# Matrice.net
KiCad netlist of a schematic drawn in Altium Designer
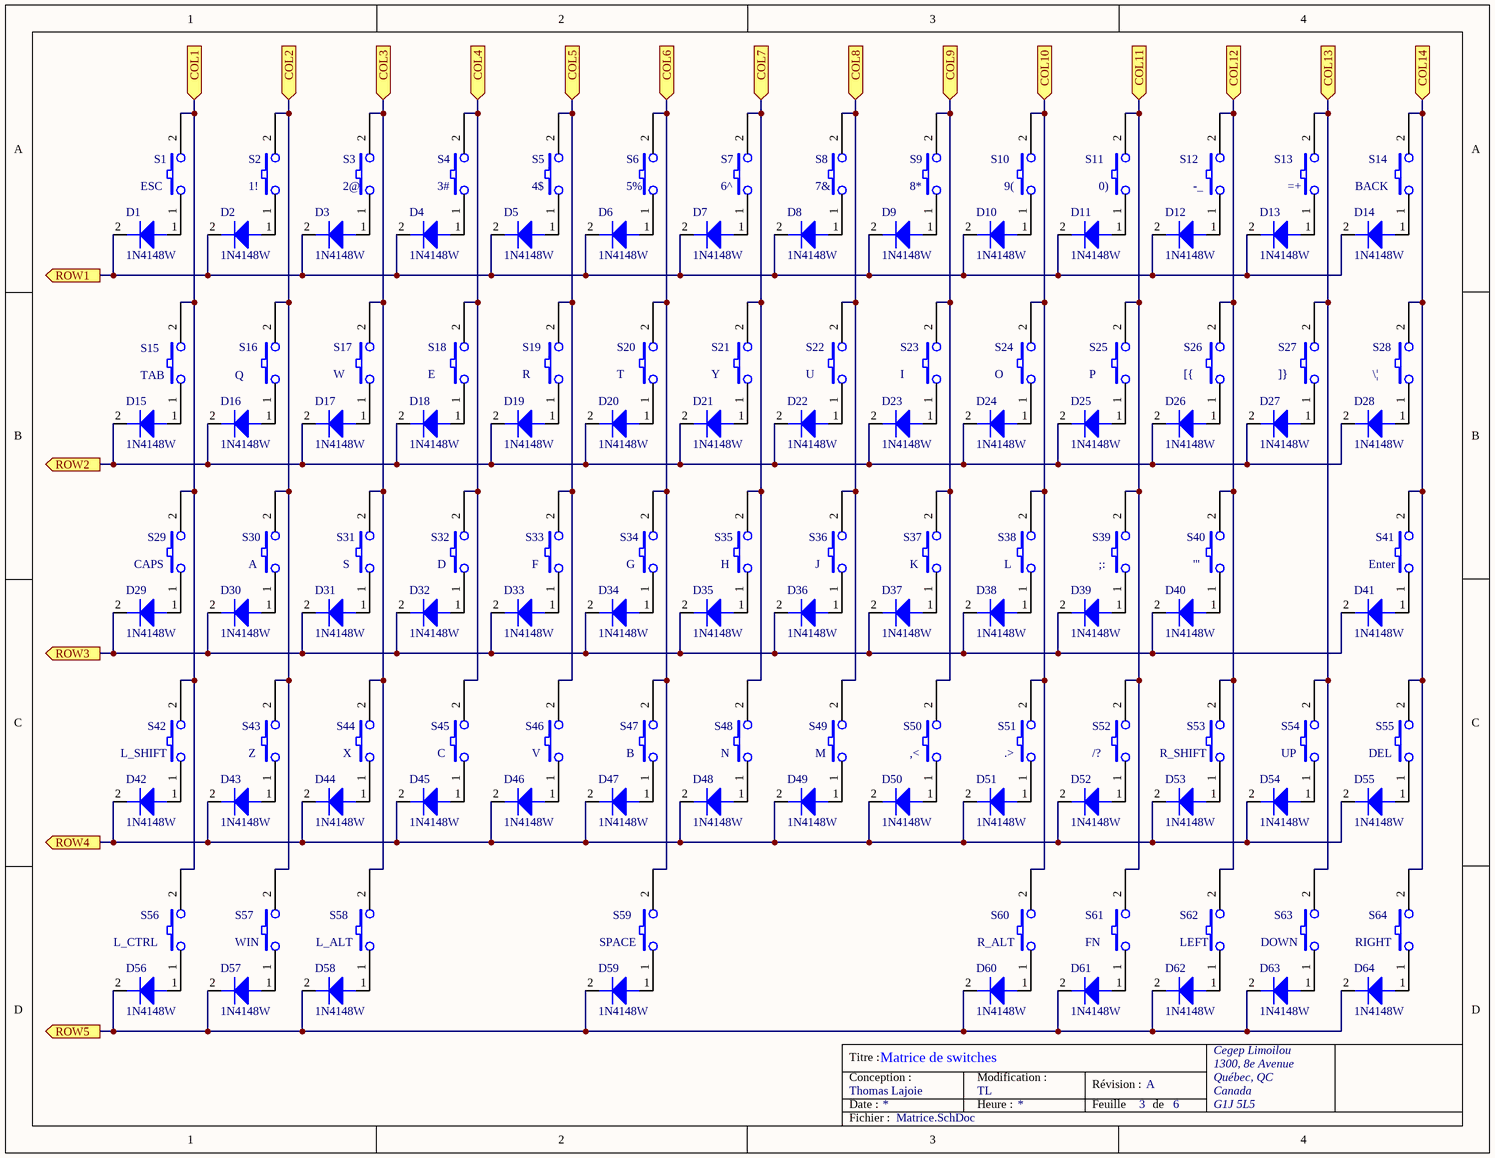
[diagram p0: Matrice.SchDoc]

(export (version "E")
  (design (tool "Eeschema 10.0.6"))
  (components
    (comp (ref "D1")
      (value "1N4148W")
      (footprint "1N4148W(SOD123)")
      (fields (field (name "LCSC PART #") "C2099"))
      (libsource (lib "PCBDEV_Library") (part "DIODE"))
    )
    (comp (ref "D2")
      (value "1N4148W")
      (footprint "1N4148W(SOD123)")
      (fields (field (name "LCSC PART #") "C2099"))
      (libsource (lib "PCBDEV_Library") (part "DIODE"))
    )
    (comp (ref "D3")
      (value "1N4148W")
      (footprint "1N4148W(SOD123)")
      (fields (field (name "LCSC PART #") "C2099"))
      (libsource (lib "PCBDEV_Library") (part "DIODE"))
    )
    (comp (ref "D4")
      (value "1N4148W")
      (footprint "1N4148W(SOD123)")
      (fields (field (name "LCSC PART #") "C2099"))
      (libsource (lib "PCBDEV_Library") (part "DIODE"))
    )
    (comp (ref "D5")
      (value "1N4148W")
      (footprint "1N4148W(SOD123)")
      (fields (field (name "LCSC PART #") "C2099"))
      (libsource (lib "PCBDEV_Library") (part "DIODE"))
    )
    (comp (ref "D6")
      (value "1N4148W")
      (footprint "1N4148W(SOD123)")
      (fields (field (name "LCSC PART #") "C2099"))
      (libsource (lib "PCBDEV_Library") (part "DIODE"))
    )
    (comp (ref "D7")
      (value "1N4148W")
      (footprint "1N4148W(SOD123)")
      (fields (field (name "LCSC PART #") "C2099"))
      (libsource (lib "PCBDEV_Library") (part "DIODE"))
    )
    (comp (ref "D8")
      (value "1N4148W")
      (footprint "1N4148W(SOD123)")
      (fields (field (name "LCSC PART #") "C2099"))
      (libsource (lib "PCBDEV_Library") (part "DIODE"))
    )
    (comp (ref "D9")
      (value "1N4148W")
      (footprint "1N4148W(SOD123)")
      (fields (field (name "LCSC PART #") "C2099"))
      (libsource (lib "PCBDEV_Library") (part "DIODE"))
    )
    (comp (ref "D10")
      (value "1N4148W")
      (footprint "1N4148W(SOD123)")
      (fields (field (name "LCSC PART #") "C2099"))
      (libsource (lib "PCBDEV_Library") (part "DIODE"))
    )
    (comp (ref "D11")
      (value "1N4148W")
      (footprint "1N4148W(SOD123)")
      (fields (field (name "LCSC PART #") "C2099"))
      (libsource (lib "PCBDEV_Library") (part "DIODE"))
    )
    (comp (ref "D12")
      (value "1N4148W")
      (footprint "1N4148W(SOD123)")
      (fields (field (name "LCSC PART #") "C2099"))
      (libsource (lib "PCBDEV_Library") (part "DIODE"))
    )
    (comp (ref "D13")
      (value "1N4148W")
      (footprint "1N4148W(SOD123)")
      (fields (field (name "LCSC PART #") "C2099"))
      (libsource (lib "PCBDEV_Library") (part "DIODE"))
    )
    (comp (ref "D14")
      (value "1N4148W")
      (footprint "1N4148W(SOD123)")
      (fields (field (name "LCSC PART #") "C2099"))
      (libsource (lib "PCBDEV_Library") (part "DIODE"))
    )
    (comp (ref "D15")
      (value "1N4148W")
      (footprint "1N4148W(SOD123)")
      (fields (field (name "LCSC PART #") "C2099"))
      (libsource (lib "PCBDEV_Library") (part "DIODE"))
    )
    (comp (ref "D16")
      (value "1N4148W")
      (footprint "1N4148W(SOD123)")
      (fields (field (name "LCSC PART #") "C2099"))
      (libsource (lib "PCBDEV_Library") (part "DIODE"))
    )
    (comp (ref "D17")
      (value "1N4148W")
      (footprint "1N4148W(SOD123)")
      (fields (field (name "LCSC PART #") "C2099"))
      (libsource (lib "PCBDEV_Library") (part "DIODE"))
    )
    (comp (ref "D18")
      (value "1N4148W")
      (footprint "1N4148W(SOD123)")
      (fields (field (name "LCSC PART #") "C2099"))
      (libsource (lib "PCBDEV_Library") (part "DIODE"))
    )
    (comp (ref "D19")
      (value "1N4148W")
      (footprint "1N4148W(SOD123)")
      (fields (field (name "LCSC PART #") "C2099"))
      (libsource (lib "PCBDEV_Library") (part "DIODE"))
    )
    (comp (ref "D20")
      (value "1N4148W")
      (footprint "1N4148W(SOD123)")
      (fields (field (name "LCSC PART #") "C2099"))
      (libsource (lib "PCBDEV_Library") (part "DIODE"))
    )
    (comp (ref "D21")
      (value "1N4148W")
      (footprint "1N4148W(SOD123)")
      (fields (field (name "LCSC PART #") "C2099"))
      (libsource (lib "PCBDEV_Library") (part "DIODE"))
    )
    (comp (ref "D22")
      (value "1N4148W")
      (footprint "1N4148W(SOD123)")
      (fields (field (name "LCSC PART #") "C2099"))
      (libsource (lib "PCBDEV_Library") (part "DIODE"))
    )
    (comp (ref "D23")
      (value "1N4148W")
      (footprint "1N4148W(SOD123)")
      (fields (field (name "LCSC PART #") "C2099"))
      (libsource (lib "PCBDEV_Library") (part "DIODE"))
    )
    (comp (ref "D24")
      (value "1N4148W")
      (footprint "1N4148W(SOD123)")
      (fields (field (name "LCSC PART #") "C2099"))
      (libsource (lib "PCBDEV_Library") (part "DIODE"))
    )
    (comp (ref "D25")
      (value "1N4148W")
      (footprint "1N4148W(SOD123)")
      (fields (field (name "LCSC PART #") "C2099"))
      (libsource (lib "PCBDEV_Library") (part "DIODE"))
    )
    (comp (ref "D26")
      (value "1N4148W")
      (footprint "1N4148W(SOD123)")
      (fields (field (name "LCSC PART #") "C2099"))
      (libsource (lib "PCBDEV_Library") (part "DIODE"))
    )
    (comp (ref "D27")
      (value "1N4148W")
      (footprint "1N4148W(SOD123)")
      (fields (field (name "LCSC PART #") "C2099"))
      (libsource (lib "PCBDEV_Library") (part "DIODE"))
    )
    (comp (ref "D28")
      (value "1N4148W")
      (footprint "1N4148W(SOD123)")
      (fields (field (name "LCSC PART #") "C2099"))
      (libsource (lib "PCBDEV_Library") (part "DIODE"))
    )
    (comp (ref "D29")
      (value "1N4148W")
      (footprint "1N4148W(SOD123)")
      (fields (field (name "LCSC PART #") "C2099"))
      (libsource (lib "PCBDEV_Library") (part "DIODE"))
    )
    (comp (ref "D30")
      (value "1N4148W")
      (footprint "1N4148W(SOD123)")
      (fields (field (name "LCSC PART #") "C2099"))
      (libsource (lib "PCBDEV_Library") (part "DIODE"))
    )
    (comp (ref "D31")
      (value "1N4148W")
      (footprint "1N4148W(SOD123)")
      (fields (field (name "LCSC PART #") "C2099"))
      (libsource (lib "PCBDEV_Library") (part "DIODE"))
    )
    (comp (ref "D32")
      (value "1N4148W")
      (footprint "1N4148W(SOD123)")
      (fields (field (name "LCSC PART #") "C2099"))
      (libsource (lib "PCBDEV_Library") (part "DIODE"))
    )
    (comp (ref "D33")
      (value "1N4148W")
      (footprint "1N4148W(SOD123)")
      (fields (field (name "LCSC PART #") "C2099"))
      (libsource (lib "PCBDEV_Library") (part "DIODE"))
    )
    (comp (ref "D34")
      (value "1N4148W")
      (footprint "1N4148W(SOD123)")
      (fields (field (name "LCSC PART #") "C2099"))
      (libsource (lib "PCBDEV_Library") (part "DIODE"))
    )
    (comp (ref "D35")
      (value "1N4148W")
      (footprint "1N4148W(SOD123)")
      (fields (field (name "LCSC PART #") "C2099"))
      (libsource (lib "PCBDEV_Library") (part "DIODE"))
    )
    (comp (ref "D36")
      (value "1N4148W")
      (footprint "1N4148W(SOD123)")
      (fields (field (name "LCSC PART #") "C2099"))
      (libsource (lib "PCBDEV_Library") (part "DIODE"))
    )
    (comp (ref "D37")
      (value "1N4148W")
      (footprint "1N4148W(SOD123)")
      (fields (field (name "LCSC PART #") "C2099"))
      (libsource (lib "PCBDEV_Library") (part "DIODE"))
    )
    (comp (ref "D38")
      (value "1N4148W")
      (footprint "1N4148W(SOD123)")
      (fields (field (name "LCSC PART #") "C2099"))
      (libsource (lib "PCBDEV_Library") (part "DIODE"))
    )
    (comp (ref "D39")
      (value "1N4148W")
      (footprint "1N4148W(SOD123)")
      (fields (field (name "LCSC PART #") "C2099"))
      (libsource (lib "PCBDEV_Library") (part "DIODE"))
    )
    (comp (ref "D40")
      (value "1N4148W")
      (footprint "1N4148W(SOD123)")
      (fields (field (name "LCSC PART #") "C2099"))
      (libsource (lib "PCBDEV_Library") (part "DIODE"))
    )
    (comp (ref "D41")
      (value "1N4148W")
      (footprint "1N4148W(SOD123)")
      (fields (field (name "LCSC PART #") "C2099"))
      (libsource (lib "PCBDEV_Library") (part "DIODE"))
    )
    (comp (ref "D42")
      (value "1N4148W")
      (footprint "1N4148W(SOD123)")
      (fields (field (name "LCSC PART #") "C2099"))
      (libsource (lib "PCBDEV_Library") (part "DIODE"))
    )
    (comp (ref "D43")
      (value "1N4148W")
      (footprint "1N4148W(SOD123)")
      (fields (field (name "LCSC PART #") "C2099"))
      (libsource (lib "PCBDEV_Library") (part "DIODE"))
    )
    (comp (ref "D44")
      (value "1N4148W")
      (footprint "1N4148W(SOD123)")
      (fields (field (name "LCSC PART #") "C2099"))
      (libsource (lib "PCBDEV_Library") (part "DIODE"))
    )
    (comp (ref "D45")
      (value "1N4148W")
      (footprint "1N4148W(SOD123)")
      (fields (field (name "LCSC PART #") "C2099"))
      (libsource (lib "PCBDEV_Library") (part "DIODE"))
    )
    (comp (ref "D46")
      (value "1N4148W")
      (footprint "1N4148W(SOD123)")
      (fields (field (name "LCSC PART #") "C2099"))
      (libsource (lib "PCBDEV_Library") (part "DIODE"))
    )
    (comp (ref "D47")
      (value "1N4148W")
      (footprint "1N4148W(SOD123)")
      (fields (field (name "LCSC PART #") "C2099"))
      (libsource (lib "PCBDEV_Library") (part "DIODE"))
    )
    (comp (ref "D48")
      (value "1N4148W")
      (footprint "1N4148W(SOD123)")
      (fields (field (name "LCSC PART #") "C2099"))
      (libsource (lib "PCBDEV_Library") (part "DIODE"))
    )
    (comp (ref "D49")
      (value "1N4148W")
      (footprint "1N4148W(SOD123)")
      (fields (field (name "LCSC PART #") "C2099"))
      (libsource (lib "PCBDEV_Library") (part "DIODE"))
    )
    (comp (ref "D50")
      (value "1N4148W")
      (footprint "1N4148W(SOD123)")
      (fields (field (name "LCSC PART #") "C2099"))
      (libsource (lib "PCBDEV_Library") (part "DIODE"))
    )
    (comp (ref "D51")
      (value "1N4148W")
      (footprint "1N4148W(SOD123)")
      (fields (field (name "LCSC PART #") "C2099"))
      (libsource (lib "PCBDEV_Library") (part "DIODE"))
    )
    (comp (ref "D52")
      (value "1N4148W")
      (footprint "1N4148W(SOD123)")
      (fields (field (name "LCSC PART #") "C2099"))
      (libsource (lib "PCBDEV_Library") (part "DIODE"))
    )
    (comp (ref "D53")
      (value "1N4148W")
      (footprint "1N4148W(SOD123)")
      (fields (field (name "LCSC PART #") "C2099"))
      (libsource (lib "PCBDEV_Library") (part "DIODE"))
    )
    (comp (ref "D54")
      (value "1N4148W")
      (footprint "1N4148W(SOD123)")
      (fields (field (name "LCSC PART #") "C2099"))
      (libsource (lib "PCBDEV_Library") (part "DIODE"))
    )
    (comp (ref "D55")
      (value "1N4148W")
      (footprint "1N4148W(SOD123)")
      (fields (field (name "LCSC PART #") "C2099"))
      (libsource (lib "PCBDEV_Library") (part "DIODE"))
    )
    (comp (ref "D56")
      (value "1N4148W")
      (footprint "1N4148W(SOD123)")
      (fields (field (name "LCSC PART #") "C2099"))
      (libsource (lib "PCBDEV_Library") (part "DIODE"))
    )
    (comp (ref "D57")
      (value "1N4148W")
      (footprint "1N4148W(SOD123)")
      (fields (field (name "LCSC PART #") "C2099"))
      (libsource (lib "PCBDEV_Library") (part "DIODE"))
    )
    (comp (ref "D58")
      (value "1N4148W")
      (footprint "1N4148W(SOD123)")
      (fields (field (name "LCSC PART #") "C2099"))
      (libsource (lib "PCBDEV_Library") (part "DIODE"))
    )
    (comp (ref "D59")
      (value "1N4148W")
      (footprint "1N4148W(SOD123)")
      (fields (field (name "LCSC PART #") "C2099"))
      (libsource (lib "PCBDEV_Library") (part "DIODE"))
    )
    (comp (ref "D60")
      (value "1N4148W")
      (footprint "1N4148W(SOD123)")
      (fields (field (name "LCSC PART #") "C2099"))
      (libsource (lib "PCBDEV_Library") (part "DIODE"))
    )
    (comp (ref "D61")
      (value "1N4148W")
      (footprint "1N4148W(SOD123)")
      (fields (field (name "LCSC PART #") "C2099"))
      (libsource (lib "PCBDEV_Library") (part "DIODE"))
    )
    (comp (ref "D62")
      (value "1N4148W")
      (footprint "1N4148W(SOD123)")
      (fields (field (name "LCSC PART #") "C2099"))
      (libsource (lib "PCBDEV_Library") (part "DIODE"))
    )
    (comp (ref "D63")
      (value "1N4148W")
      (footprint "1N4148W(SOD123)")
      (fields (field (name "LCSC PART #") "C2099"))
      (libsource (lib "PCBDEV_Library") (part "DIODE"))
    )
    (comp (ref "D64")
      (value "1N4148W")
      (footprint "1N4148W(SOD123)")
      (fields (field (name "LCSC PART #") "C2099"))
      (libsource (lib "PCBDEV_Library") (part "DIODE"))
    )
    (comp (ref "S1")
      (value "ESC")
      (footprint "GATERON_LOWPROFILE_HOTSWAP_SOCKET")
      (libsource (lib "PCBDEV_Library") (part "SW PUSHBUTTON"))
    )
    (comp (ref "S2")
      (value "1!")
      (footprint "GATERON_LOWPROFILE_HOTSWAP_SOCKET")
      (libsource (lib "PCBDEV_Library") (part "SW PUSHBUTTON"))
    )
    (comp (ref "S3")
      (value "2@")
      (footprint "GATERON_LOWPROFILE_HOTSWAP_SOCKET")
      (libsource (lib "PCBDEV_Library") (part "SW PUSHBUTTON"))
    )
    (comp (ref "S4")
      (value "3#")
      (footprint "GATERON_LOWPROFILE_HOTSWAP_SOCKET")
      (libsource (lib "PCBDEV_Library") (part "SW PUSHBUTTON"))
    )
    (comp (ref "S5")
      (value "4$")
      (footprint "GATERON_LOWPROFILE_HOTSWAP_SOCKET")
      (libsource (lib "PCBDEV_Library") (part "SW PUSHBUTTON"))
    )
    (comp (ref "S6")
      (value "5%")
      (footprint "GATERON_LOWPROFILE_HOTSWAP_SOCKET")
      (libsource (lib "PCBDEV_Library") (part "SW PUSHBUTTON"))
    )
    (comp (ref "S7")
      (value "6^")
      (footprint "GATERON_LOWPROFILE_HOTSWAP_SOCKET")
      (libsource (lib "PCBDEV_Library") (part "SW PUSHBUTTON"))
    )
    (comp (ref "S8")
      (value "7&")
      (footprint "GATERON_LOWPROFILE_HOTSWAP_SOCKET")
      (libsource (lib "PCBDEV_Library") (part "SW PUSHBUTTON"))
    )
    (comp (ref "S9")
      (value "8*")
      (footprint "GATERON_LOWPROFILE_HOTSWAP_SOCKET")
      (libsource (lib "PCBDEV_Library") (part "SW PUSHBUTTON"))
    )
    (comp (ref "S10")
      (value "9(")
      (footprint "GATERON_LOWPROFILE_HOTSWAP_SOCKET")
      (libsource (lib "PCBDEV_Library") (part "SW PUSHBUTTON"))
    )
    (comp (ref "S11")
      (value "0)")
      (footprint "GATERON_LOWPROFILE_HOTSWAP_SOCKET")
      (libsource (lib "PCBDEV_Library") (part "SW PUSHBUTTON"))
    )
    (comp (ref "S12")
      (value "-_")
      (footprint "GATERON_LOWPROFILE_HOTSWAP_SOCKET")
      (libsource (lib "PCBDEV_Library") (part "SW PUSHBUTTON"))
    )
    (comp (ref "S13")
      (value "~")
      (footprint "GATERON_LOWPROFILE_HOTSWAP_SOCKET")
      (libsource (lib "PCBDEV_Library") (part "SW PUSHBUTTON"))
    )
    (comp (ref "S14")
      (value "BACK")
      (footprint "GATERON_LOWPROFILE_HOTSWAP_SOCKET")
      (libsource (lib "PCBDEV_Library") (part "SW PUSHBUTTON"))
    )
    (comp (ref "S15")
      (value "TAB")
      (footprint "GATERON_LOWPROFILE_HOTSWAP_SOCKET")
      (libsource (lib "PCBDEV_Library") (part "SW PUSHBUTTON"))
    )
    (comp (ref "S16")
      (value "Q")
      (footprint "GATERON_LOWPROFILE_HOTSWAP_SOCKET")
      (libsource (lib "PCBDEV_Library") (part "SW PUSHBUTTON"))
    )
    (comp (ref "S17")
      (value "W")
      (footprint "GATERON_LOWPROFILE_HOTSWAP_SOCKET")
      (libsource (lib "PCBDEV_Library") (part "SW PUSHBUTTON"))
    )
    (comp (ref "S18")
      (value "E")
      (footprint "GATERON_LOWPROFILE_HOTSWAP_SOCKET")
      (libsource (lib "PCBDEV_Library") (part "SW PUSHBUTTON"))
    )
    (comp (ref "S19")
      (value "R")
      (footprint "GATERON_LOWPROFILE_HOTSWAP_SOCKET")
      (libsource (lib "PCBDEV_Library") (part "SW PUSHBUTTON"))
    )
    (comp (ref "S20")
      (value "T")
      (footprint "GATERON_LOWPROFILE_HOTSWAP_SOCKET")
      (libsource (lib "PCBDEV_Library") (part "SW PUSHBUTTON"))
    )
    (comp (ref "S21")
      (value "Y")
      (footprint "GATERON_LOWPROFILE_HOTSWAP_SOCKET")
      (libsource (lib "PCBDEV_Library") (part "SW PUSHBUTTON"))
    )
    (comp (ref "S22")
      (value "U")
      (footprint "GATERON_LOWPROFILE_HOTSWAP_SOCKET")
      (libsource (lib "PCBDEV_Library") (part "SW PUSHBUTTON"))
    )
    (comp (ref "S23")
      (value "I")
      (footprint "GATERON_LOWPROFILE_HOTSWAP_SOCKET")
      (libsource (lib "PCBDEV_Library") (part "SW PUSHBUTTON"))
    )
    (comp (ref "S24")
      (value "O")
      (footprint "GATERON_LOWPROFILE_HOTSWAP_SOCKET")
      (libsource (lib "PCBDEV_Library") (part "SW PUSHBUTTON"))
    )
    (comp (ref "S25")
      (value "P")
      (footprint "GATERON_LOWPROFILE_HOTSWAP_SOCKET")
      (libsource (lib "PCBDEV_Library") (part "SW PUSHBUTTON"))
    )
    (comp (ref "S26")
      (value "[{")
      (footprint "GATERON_LOWPROFILE_HOTSWAP_SOCKET")
      (libsource (lib "PCBDEV_Library") (part "SW PUSHBUTTON"))
    )
    (comp (ref "S27")
      (value "]}")
      (footprint "GATERON_LOWPROFILE_HOTSWAP_SOCKET")
      (libsource (lib "PCBDEV_Library") (part "SW PUSHBUTTON"))
    )
    (comp (ref "S28")
      (value "\\¦")
      (footprint "GATERON_LOWPROFILE_HOTSWAP_SOCKET")
      (libsource (lib "PCBDEV_Library") (part "SW PUSHBUTTON"))
    )
    (comp (ref "S29")
      (value "CAPS")
      (footprint "GATERON_LOWPROFILE_HOTSWAP_SOCKET")
      (libsource (lib "PCBDEV_Library") (part "SW PUSHBUTTON"))
    )
    (comp (ref "S30")
      (value "A")
      (footprint "GATERON_LOWPROFILE_HOTSWAP_SOCKET")
      (libsource (lib "PCBDEV_Library") (part "SW PUSHBUTTON"))
    )
    (comp (ref "S31")
      (value "S")
      (footprint "GATERON_LOWPROFILE_HOTSWAP_SOCKET")
      (libsource (lib "PCBDEV_Library") (part "SW PUSHBUTTON"))
    )
    (comp (ref "S32")
      (value "D")
      (footprint "GATERON_LOWPROFILE_HOTSWAP_SOCKET")
      (libsource (lib "PCBDEV_Library") (part "SW PUSHBUTTON"))
    )
    (comp (ref "S33")
      (value "F")
      (footprint "GATERON_LOWPROFILE_HOTSWAP_SOCKET")
      (libsource (lib "PCBDEV_Library") (part "SW PUSHBUTTON"))
    )
    (comp (ref "S34")
      (value "G")
      (footprint "GATERON_LOWPROFILE_HOTSWAP_SOCKET")
      (libsource (lib "PCBDEV_Library") (part "SW PUSHBUTTON"))
    )
    (comp (ref "S35")
      (value "H")
      (footprint "GATERON_LOWPROFILE_HOTSWAP_SOCKET")
      (libsource (lib "PCBDEV_Library") (part "SW PUSHBUTTON"))
    )
    (comp (ref "S36")
      (value "J")
      (footprint "GATERON_LOWPROFILE_HOTSWAP_SOCKET")
      (libsource (lib "PCBDEV_Library") (part "SW PUSHBUTTON"))
    )
    (comp (ref "S37")
      (value "K")
      (footprint "GATERON_LOWPROFILE_HOTSWAP_SOCKET")
      (libsource (lib "PCBDEV_Library") (part "SW PUSHBUTTON"))
    )
    (comp (ref "S38")
      (value "L")
      (footprint "GATERON_LOWPROFILE_HOTSWAP_SOCKET")
      (libsource (lib "PCBDEV_Library") (part "SW PUSHBUTTON"))
    )
    (comp (ref "S39")
      (value ";:")
      (footprint "GATERON_LOWPROFILE_HOTSWAP_SOCKET")
      (libsource (lib "PCBDEV_Library") (part "SW PUSHBUTTON"))
    )
    (comp (ref "S40")
      (value "'\"")
      (footprint "GATERON_LOWPROFILE_HOTSWAP_SOCKET")
      (libsource (lib "PCBDEV_Library") (part "SW PUSHBUTTON"))
    )
    (comp (ref "S41")
      (value "Enter")
      (footprint "GATERON_LOWPROFILE_HOTSWAP_SOCKET")
      (libsource (lib "PCBDEV_Library") (part "SW PUSHBUTTON"))
    )
    (comp (ref "S42")
      (value "L_SHIFT")
      (footprint "GATERON_LOWPROFILE_HOTSWAP_SOCKET")
      (libsource (lib "PCBDEV_Library") (part "SW PUSHBUTTON"))
    )
    (comp (ref "S43")
      (value "Z")
      (footprint "GATERON_LOWPROFILE_HOTSWAP_SOCKET")
      (libsource (lib "PCBDEV_Library") (part "SW PUSHBUTTON"))
    )
    (comp (ref "S44")
      (value "X")
      (footprint "GATERON_LOWPROFILE_HOTSWAP_SOCKET")
      (libsource (lib "PCBDEV_Library") (part "SW PUSHBUTTON"))
    )
    (comp (ref "S45")
      (value "C")
      (footprint "GATERON_LOWPROFILE_HOTSWAP_SOCKET")
      (libsource (lib "PCBDEV_Library") (part "SW PUSHBUTTON"))
    )
    (comp (ref "S46")
      (value "V")
      (footprint "GATERON_LOWPROFILE_HOTSWAP_SOCKET")
      (libsource (lib "PCBDEV_Library") (part "SW PUSHBUTTON"))
    )
    (comp (ref "S47")
      (value "B")
      (footprint "GATERON_LOWPROFILE_HOTSWAP_SOCKET")
      (libsource (lib "PCBDEV_Library") (part "SW PUSHBUTTON"))
    )
    (comp (ref "S48")
      (value "N")
      (footprint "GATERON_LOWPROFILE_HOTSWAP_SOCKET")
      (libsource (lib "PCBDEV_Library") (part "SW PUSHBUTTON"))
    )
    (comp (ref "S49")
      (value "M")
      (footprint "GATERON_LOWPROFILE_HOTSWAP_SOCKET")
      (libsource (lib "PCBDEV_Library") (part "SW PUSHBUTTON"))
    )
    (comp (ref "S50")
      (value ",<")
      (footprint "GATERON_LOWPROFILE_HOTSWAP_SOCKET")
      (libsource (lib "PCBDEV_Library") (part "SW PUSHBUTTON"))
    )
    (comp (ref "S51")
      (value ".>")
      (footprint "GATERON_LOWPROFILE_HOTSWAP_SOCKET")
      (libsource (lib "PCBDEV_Library") (part "SW PUSHBUTTON"))
    )
    (comp (ref "S52")
      (value "/?")
      (footprint "GATERON_LOWPROFILE_HOTSWAP_SOCKET")
      (libsource (lib "PCBDEV_Library") (part "SW PUSHBUTTON"))
    )
    (comp (ref "S53")
      (value "R_SHIFT")
      (footprint "GATERON_LOWPROFILE_HOTSWAP_SOCKET")
      (libsource (lib "PCBDEV_Library") (part "SW PUSHBUTTON"))
    )
    (comp (ref "S54")
      (value "UP")
      (footprint "GATERON_LOWPROFILE_HOTSWAP_SOCKET")
      (libsource (lib "PCBDEV_Library") (part "SW PUSHBUTTON"))
    )
    (comp (ref "S55")
      (value "DEL")
      (footprint "GATERON_LOWPROFILE_HOTSWAP_SOCKET")
      (libsource (lib "PCBDEV_Library") (part "SW PUSHBUTTON"))
    )
    (comp (ref "S56")
      (value "L_CTRL")
      (footprint "GATERON_LOWPROFILE_HOTSWAP_SOCKET")
      (libsource (lib "PCBDEV_Library") (part "SW PUSHBUTTON"))
    )
    (comp (ref "S57")
      (value "WIN")
      (footprint "GATERON_LOWPROFILE_HOTSWAP_SOCKET")
      (libsource (lib "PCBDEV_Library") (part "SW PUSHBUTTON"))
    )
    (comp (ref "S58")
      (value "L_ALT")
      (footprint "GATERON_LOWPROFILE_HOTSWAP_SOCKET")
      (libsource (lib "PCBDEV_Library") (part "SW PUSHBUTTON"))
    )
    (comp (ref "S59")
      (value "SPACE")
      (footprint "GATERON_LOWPROFILE_HOTSWAP_SOCKET")
      (libsource (lib "PCBDEV_Library") (part "SW PUSHBUTTON"))
    )
    (comp (ref "S60")
      (value "R_ALT")
      (footprint "GATERON_LOWPROFILE_HOTSWAP_SOCKET")
      (libsource (lib "PCBDEV_Library") (part "SW PUSHBUTTON"))
    )
    (comp (ref "S61")
      (value "FN")
      (footprint "GATERON_LOWPROFILE_HOTSWAP_SOCKET")
      (libsource (lib "PCBDEV_Library") (part "SW PUSHBUTTON"))
    )
    (comp (ref "S62")
      (value "LEFT")
      (footprint "GATERON_LOWPROFILE_HOTSWAP_SOCKET")
      (libsource (lib "PCBDEV_Library") (part "SW PUSHBUTTON"))
    )
    (comp (ref "S63")
      (value "DOWN")
      (footprint "GATERON_LOWPROFILE_HOTSWAP_SOCKET")
      (libsource (lib "PCBDEV_Library") (part "SW PUSHBUTTON"))
    )
    (comp (ref "S64")
      (value "RIGHT")
      (footprint "GATERON_LOWPROFILE_HOTSWAP_SOCKET")
      (libsource (lib "PCBDEV_Library") (part "SW PUSHBUTTON"))
    )
  )
  (nets
    (net (code "1") (name "/COL1") (class "Default")
      (node (ref "S1") (pin "2") (pinfunction "2_2") (pintype "passive"))
      (node (ref "S15") (pin "2") (pinfunction "2_2") (pintype "passive"))
      (node (ref "S29") (pin "2") (pinfunction "2_2") (pintype "passive"))
      (node (ref "S42") (pin "2") (pinfunction "2_2") (pintype "passive"))
      (node (ref "S56") (pin "2") (pinfunction "2_2") (pintype "passive"))
    )
    (net (code "2") (name "/COL2") (class "Default")
      (node (ref "S16") (pin "2") (pinfunction "2_2") (pintype "passive"))
      (node (ref "S2") (pin "2") (pinfunction "2_2") (pintype "passive"))
      (node (ref "S30") (pin "2") (pinfunction "2_2") (pintype "passive"))
      (node (ref "S43") (pin "2") (pinfunction "2_2") (pintype "passive"))
      (node (ref "S57") (pin "2") (pinfunction "2_2") (pintype "passive"))
    )
    (net (code "3") (name "/COL3") (class "Default")
      (node (ref "S17") (pin "2") (pinfunction "2_2") (pintype "passive"))
      (node (ref "S3") (pin "2") (pinfunction "2_2") (pintype "passive"))
      (node (ref "S31") (pin "2") (pinfunction "2_2") (pintype "passive"))
      (node (ref "S44") (pin "2") (pinfunction "2_2") (pintype "passive"))
      (node (ref "S58") (pin "2") (pinfunction "2_2") (pintype "passive"))
    )
    (net (code "4") (name "/COL4") (class "Default")
      (node (ref "S18") (pin "2") (pinfunction "2_2") (pintype "passive"))
      (node (ref "S32") (pin "2") (pinfunction "2_2") (pintype "passive"))
      (node (ref "S4") (pin "2") (pinfunction "2_2") (pintype "passive"))
      (node (ref "S45") (pin "2") (pinfunction "2_2") (pintype "passive"))
    )
    (net (code "5") (name "/COL5") (class "Default")
      (node (ref "S19") (pin "2") (pinfunction "2_2") (pintype "passive"))
      (node (ref "S33") (pin "2") (pinfunction "2_2") (pintype "passive"))
      (node (ref "S46") (pin "2") (pinfunction "2_2") (pintype "passive"))
      (node (ref "S5") (pin "2") (pinfunction "2_2") (pintype "passive"))
    )
    (net (code "6") (name "/COL6") (class "Default")
      (node (ref "S20") (pin "2") (pinfunction "2_2") (pintype "passive"))
      (node (ref "S34") (pin "2") (pinfunction "2_2") (pintype "passive"))
      (node (ref "S47") (pin "2") (pinfunction "2_2") (pintype "passive"))
      (node (ref "S59") (pin "2") (pinfunction "2_2") (pintype "passive"))
      (node (ref "S6") (pin "2") (pinfunction "2_2") (pintype "passive"))
    )
    (net (code "7") (name "/COL7") (class "Default")
      (node (ref "S21") (pin "2") (pinfunction "2_2") (pintype "passive"))
      (node (ref "S35") (pin "2") (pinfunction "2_2") (pintype "passive"))
      (node (ref "S48") (pin "2") (pinfunction "2_2") (pintype "passive"))
      (node (ref "S7") (pin "2") (pinfunction "2_2") (pintype "passive"))
    )
    (net (code "8") (name "/COL8") (class "Default")
      (node (ref "S22") (pin "2") (pinfunction "2_2") (pintype "passive"))
      (node (ref "S36") (pin "2") (pinfunction "2_2") (pintype "passive"))
      (node (ref "S49") (pin "2") (pinfunction "2_2") (pintype "passive"))
      (node (ref "S8") (pin "2") (pinfunction "2_2") (pintype "passive"))
    )
    (net (code "9") (name "/COL9") (class "Default")
      (node (ref "S23") (pin "2") (pinfunction "2_2") (pintype "passive"))
      (node (ref "S37") (pin "2") (pinfunction "2_2") (pintype "passive"))
      (node (ref "S50") (pin "2") (pinfunction "2_2") (pintype "passive"))
      (node (ref "S9") (pin "2") (pinfunction "2_2") (pintype "passive"))
    )
    (net (code "10") (name "/COL10") (class "Default")
      (node (ref "S10") (pin "2") (pinfunction "2_2") (pintype "passive"))
      (node (ref "S24") (pin "2") (pinfunction "2_2") (pintype "passive"))
      (node (ref "S38") (pin "2") (pinfunction "2_2") (pintype "passive"))
      (node (ref "S51") (pin "2") (pinfunction "2_2") (pintype "passive"))
      (node (ref "S60") (pin "2") (pinfunction "2_2") (pintype "passive"))
    )
    (net (code "11") (name "/COL11") (class "Default")
      (node (ref "S11") (pin "2") (pinfunction "2_2") (pintype "passive"))
      (node (ref "S25") (pin "2") (pinfunction "2_2") (pintype "passive"))
      (node (ref "S39") (pin "2") (pinfunction "2_2") (pintype "passive"))
      (node (ref "S52") (pin "2") (pinfunction "2_2") (pintype "passive"))
      (node (ref "S61") (pin "2") (pinfunction "2_2") (pintype "passive"))
    )
    (net (code "12") (name "/COL12") (class "Default")
      (node (ref "S12") (pin "2") (pinfunction "2_2") (pintype "passive"))
      (node (ref "S26") (pin "2") (pinfunction "2_2") (pintype "passive"))
      (node (ref "S40") (pin "2") (pinfunction "2_2") (pintype "passive"))
      (node (ref "S53") (pin "2") (pinfunction "2_2") (pintype "passive"))
      (node (ref "S62") (pin "2") (pinfunction "2_2") (pintype "passive"))
    )
    (net (code "13") (name "/COL13") (class "Default")
      (node (ref "S13") (pin "2") (pinfunction "2_2") (pintype "passive"))
      (node (ref "S27") (pin "2") (pinfunction "2_2") (pintype "passive"))
      (node (ref "S54") (pin "2") (pinfunction "2_2") (pintype "passive"))
      (node (ref "S63") (pin "2") (pinfunction "2_2") (pintype "passive"))
    )
    (net (code "14") (name "/COL14") (class "Default")
      (node (ref "S14") (pin "2") (pinfunction "2_2") (pintype "passive"))
      (node (ref "S28") (pin "2") (pinfunction "2_2") (pintype "passive"))
      (node (ref "S41") (pin "2") (pinfunction "2_2") (pintype "passive"))
      (node (ref "S55") (pin "2") (pinfunction "2_2") (pintype "passive"))
      (node (ref "S64") (pin "2") (pinfunction "2_2") (pintype "passive"))
    )
    (net (code "15") (name "/ROW1") (class "Default")
      (node (ref "D1") (pin "2") (pinfunction "CATHODE_2") (pintype "passive"))
      (node (ref "D10") (pin "2") (pinfunction "CATHODE_2") (pintype "passive"))
      (node (ref "D11") (pin "2") (pinfunction "CATHODE_2") (pintype "passive"))
      (node (ref "D12") (pin "2") (pinfunction "CATHODE_2") (pintype "passive"))
      (node (ref "D13") (pin "2") (pinfunction "CATHODE_2") (pintype "passive"))
      (node (ref "D14") (pin "2") (pinfunction "CATHODE_2") (pintype "passive"))
      (node (ref "D2") (pin "2") (pinfunction "CATHODE_2") (pintype "passive"))
      (node (ref "D3") (pin "2") (pinfunction "CATHODE_2") (pintype "passive"))
      (node (ref "D4") (pin "2") (pinfunction "CATHODE_2") (pintype "passive"))
      (node (ref "D5") (pin "2") (pinfunction "CATHODE_2") (pintype "passive"))
      (node (ref "D6") (pin "2") (pinfunction "CATHODE_2") (pintype "passive"))
      (node (ref "D7") (pin "2") (pinfunction "CATHODE_2") (pintype "passive"))
      (node (ref "D8") (pin "2") (pinfunction "CATHODE_2") (pintype "passive"))
      (node (ref "D9") (pin "2") (pinfunction "CATHODE_2") (pintype "passive"))
    )
    (net (code "16") (name "/ROW2") (class "Default")
      (node (ref "D15") (pin "2") (pinfunction "CATHODE_2") (pintype "passive"))
      (node (ref "D16") (pin "2") (pinfunction "CATHODE_2") (pintype "passive"))
      (node (ref "D17") (pin "2") (pinfunction "CATHODE_2") (pintype "passive"))
      (node (ref "D18") (pin "2") (pinfunction "CATHODE_2") (pintype "passive"))
      (node (ref "D19") (pin "2") (pinfunction "CATHODE_2") (pintype "passive"))
      (node (ref "D20") (pin "2") (pinfunction "CATHODE_2") (pintype "passive"))
      (node (ref "D21") (pin "2") (pinfunction "CATHODE_2") (pintype "passive"))
      (node (ref "D22") (pin "2") (pinfunction "CATHODE_2") (pintype "passive"))
      (node (ref "D23") (pin "2") (pinfunction "CATHODE_2") (pintype "passive"))
      (node (ref "D24") (pin "2") (pinfunction "CATHODE_2") (pintype "passive"))
      (node (ref "D25") (pin "2") (pinfunction "CATHODE_2") (pintype "passive"))
      (node (ref "D26") (pin "2") (pinfunction "CATHODE_2") (pintype "passive"))
      (node (ref "D27") (pin "2") (pinfunction "CATHODE_2") (pintype "passive"))
      (node (ref "D28") (pin "2") (pinfunction "CATHODE_2") (pintype "passive"))
    )
    (net (code "17") (name "/ROW3") (class "Default")
      (node (ref "D29") (pin "2") (pinfunction "CATHODE_2") (pintype "passive"))
      (node (ref "D30") (pin "2") (pinfunction "CATHODE_2") (pintype "passive"))
      (node (ref "D31") (pin "2") (pinfunction "CATHODE_2") (pintype "passive"))
      (node (ref "D32") (pin "2") (pinfunction "CATHODE_2") (pintype "passive"))
      (node (ref "D33") (pin "2") (pinfunction "CATHODE_2") (pintype "passive"))
      (node (ref "D34") (pin "2") (pinfunction "CATHODE_2") (pintype "passive"))
      (node (ref "D35") (pin "2") (pinfunction "CATHODE_2") (pintype "passive"))
      (node (ref "D36") (pin "2") (pinfunction "CATHODE_2") (pintype "passive"))
      (node (ref "D37") (pin "2") (pinfunction "CATHODE_2") (pintype "passive"))
      (node (ref "D38") (pin "2") (pinfunction "CATHODE_2") (pintype "passive"))
      (node (ref "D39") (pin "2") (pinfunction "CATHODE_2") (pintype "passive"))
      (node (ref "D40") (pin "2") (pinfunction "CATHODE_2") (pintype "passive"))
      (node (ref "D41") (pin "2") (pinfunction "CATHODE_2") (pintype "passive"))
    )
    (net (code "18") (name "/ROW4") (class "Default")
      (node (ref "D42") (pin "2") (pinfunction "CATHODE_2") (pintype "passive"))
      (node (ref "D43") (pin "2") (pinfunction "CATHODE_2") (pintype "passive"))
      (node (ref "D44") (pin "2") (pinfunction "CATHODE_2") (pintype "passive"))
      (node (ref "D45") (pin "2") (pinfunction "CATHODE_2") (pintype "passive"))
      (node (ref "D46") (pin "2") (pinfunction "CATHODE_2") (pintype "passive"))
      (node (ref "D47") (pin "2") (pinfunction "CATHODE_2") (pintype "passive"))
      (node (ref "D48") (pin "2") (pinfunction "CATHODE_2") (pintype "passive"))
      (node (ref "D49") (pin "2") (pinfunction "CATHODE_2") (pintype "passive"))
      (node (ref "D50") (pin "2") (pinfunction "CATHODE_2") (pintype "passive"))
      (node (ref "D51") (pin "2") (pinfunction "CATHODE_2") (pintype "passive"))
      (node (ref "D52") (pin "2") (pinfunction "CATHODE_2") (pintype "passive"))
      (node (ref "D53") (pin "2") (pinfunction "CATHODE_2") (pintype "passive"))
      (node (ref "D54") (pin "2") (pinfunction "CATHODE_2") (pintype "passive"))
      (node (ref "D55") (pin "2") (pinfunction "CATHODE_2") (pintype "passive"))
    )
    (net (code "19") (name "/ROW5") (class "Default")
      (node (ref "D56") (pin "2") (pinfunction "CATHODE_2") (pintype "passive"))
      (node (ref "D57") (pin "2") (pinfunction "CATHODE_2") (pintype "passive"))
      (node (ref "D58") (pin "2") (pinfunction "CATHODE_2") (pintype "passive"))
      (node (ref "D59") (pin "2") (pinfunction "CATHODE_2") (pintype "passive"))
      (node (ref "D60") (pin "2") (pinfunction "CATHODE_2") (pintype "passive"))
      (node (ref "D61") (pin "2") (pinfunction "CATHODE_2") (pintype "passive"))
      (node (ref "D62") (pin "2") (pinfunction "CATHODE_2") (pintype "passive"))
      (node (ref "D63") (pin "2") (pinfunction "CATHODE_2") (pintype "passive"))
      (node (ref "D64") (pin "2") (pinfunction "CATHODE_2") (pintype "passive"))
    )
    (net (code "20") (name "Net-(D1-ANODE)") (class "Default")
      (node (ref "D1") (pin "1") (pinfunction "ANODE_1") (pintype "passive"))
      (node (ref "S1") (pin "1") (pinfunction "1_1") (pintype "passive"))
    )
    (net (code "21") (name "Net-(D2-ANODE)") (class "Default")
      (node (ref "D2") (pin "1") (pinfunction "ANODE_1") (pintype "passive"))
      (node (ref "S2") (pin "1") (pinfunction "1_1") (pintype "passive"))
    )
    (net (code "22") (name "Net-(D3-ANODE)") (class "Default")
      (node (ref "D3") (pin "1") (pinfunction "ANODE_1") (pintype "passive"))
      (node (ref "S3") (pin "1") (pinfunction "1_1") (pintype "passive"))
    )
    (net (code "23") (name "Net-(D4-ANODE)") (class "Default")
      (node (ref "D4") (pin "1") (pinfunction "ANODE_1") (pintype "passive"))
      (node (ref "S4") (pin "1") (pinfunction "1_1") (pintype "passive"))
    )
    (net (code "24") (name "Net-(D5-ANODE)") (class "Default")
      (node (ref "D5") (pin "1") (pinfunction "ANODE_1") (pintype "passive"))
      (node (ref "S5") (pin "1") (pinfunction "1_1") (pintype "passive"))
    )
    (net (code "25") (name "Net-(D6-ANODE)") (class "Default")
      (node (ref "D6") (pin "1") (pinfunction "ANODE_1") (pintype "passive"))
      (node (ref "S6") (pin "1") (pinfunction "1_1") (pintype "passive"))
    )
    (net (code "26") (name "Net-(D7-ANODE)") (class "Default")
      (node (ref "D7") (pin "1") (pinfunction "ANODE_1") (pintype "passive"))
      (node (ref "S7") (pin "1") (pinfunction "1_1") (pintype "passive"))
    )
    (net (code "27") (name "Net-(D8-ANODE)") (class "Default")
      (node (ref "D8") (pin "1") (pinfunction "ANODE_1") (pintype "passive"))
      (node (ref "S8") (pin "1") (pinfunction "1_1") (pintype "passive"))
    )
    (net (code "28") (name "Net-(D9-ANODE)") (class "Default")
      (node (ref "D9") (pin "1") (pinfunction "ANODE_1") (pintype "passive"))
      (node (ref "S9") (pin "1") (pinfunction "1_1") (pintype "passive"))
    )
    (net (code "29") (name "Net-(D10-ANODE)") (class "Default")
      (node (ref "D10") (pin "1") (pinfunction "ANODE_1") (pintype "passive"))
      (node (ref "S10") (pin "1") (pinfunction "1_1") (pintype "passive"))
    )
    (net (code "30") (name "Net-(D11-ANODE)") (class "Default")
      (node (ref "D11") (pin "1") (pinfunction "ANODE_1") (pintype "passive"))
      (node (ref "S11") (pin "1") (pinfunction "1_1") (pintype "passive"))
    )
    (net (code "31") (name "Net-(D12-ANODE)") (class "Default")
      (node (ref "D12") (pin "1") (pinfunction "ANODE_1") (pintype "passive"))
      (node (ref "S12") (pin "1") (pinfunction "1_1") (pintype "passive"))
    )
    (net (code "32") (name "Net-(D13-ANODE)") (class "Default")
      (node (ref "D13") (pin "1") (pinfunction "ANODE_1") (pintype "passive"))
      (node (ref "S13") (pin "1") (pinfunction "1_1") (pintype "passive"))
    )
    (net (code "33") (name "Net-(D14-ANODE)") (class "Default")
      (node (ref "D14") (pin "1") (pinfunction "ANODE_1") (pintype "passive"))
      (node (ref "S14") (pin "1") (pinfunction "1_1") (pintype "passive"))
    )
    (net (code "34") (name "Net-(D15-ANODE)") (class "Default")
      (node (ref "D15") (pin "1") (pinfunction "ANODE_1") (pintype "passive"))
      (node (ref "S15") (pin "1") (pinfunction "1_1") (pintype "passive"))
    )
    (net (code "35") (name "Net-(D16-ANODE)") (class "Default")
      (node (ref "D16") (pin "1") (pinfunction "ANODE_1") (pintype "passive"))
      (node (ref "S16") (pin "1") (pinfunction "1_1") (pintype "passive"))
    )
    (net (code "36") (name "Net-(D17-ANODE)") (class "Default")
      (node (ref "D17") (pin "1") (pinfunction "ANODE_1") (pintype "passive"))
      (node (ref "S17") (pin "1") (pinfunction "1_1") (pintype "passive"))
    )
    (net (code "37") (name "Net-(D18-ANODE)") (class "Default")
      (node (ref "D18") (pin "1") (pinfunction "ANODE_1") (pintype "passive"))
      (node (ref "S18") (pin "1") (pinfunction "1_1") (pintype "passive"))
    )
    (net (code "38") (name "Net-(D19-ANODE)") (class "Default")
      (node (ref "D19") (pin "1") (pinfunction "ANODE_1") (pintype "passive"))
      (node (ref "S19") (pin "1") (pinfunction "1_1") (pintype "passive"))
    )
    (net (code "39") (name "Net-(D20-ANODE)") (class "Default")
      (node (ref "D20") (pin "1") (pinfunction "ANODE_1") (pintype "passive"))
      (node (ref "S20") (pin "1") (pinfunction "1_1") (pintype "passive"))
    )
    (net (code "40") (name "Net-(D21-ANODE)") (class "Default")
      (node (ref "D21") (pin "1") (pinfunction "ANODE_1") (pintype "passive"))
      (node (ref "S21") (pin "1") (pinfunction "1_1") (pintype "passive"))
    )
    (net (code "41") (name "Net-(D22-ANODE)") (class "Default")
      (node (ref "D22") (pin "1") (pinfunction "ANODE_1") (pintype "passive"))
      (node (ref "S22") (pin "1") (pinfunction "1_1") (pintype "passive"))
    )
    (net (code "42") (name "Net-(D23-ANODE)") (class "Default")
      (node (ref "D23") (pin "1") (pinfunction "ANODE_1") (pintype "passive"))
      (node (ref "S23") (pin "1") (pinfunction "1_1") (pintype "passive"))
    )
    (net (code "43") (name "Net-(D24-ANODE)") (class "Default")
      (node (ref "D24") (pin "1") (pinfunction "ANODE_1") (pintype "passive"))
      (node (ref "S24") (pin "1") (pinfunction "1_1") (pintype "passive"))
    )
    (net (code "44") (name "Net-(D25-ANODE)") (class "Default")
      (node (ref "D25") (pin "1") (pinfunction "ANODE_1") (pintype "passive"))
      (node (ref "S25") (pin "1") (pinfunction "1_1") (pintype "passive"))
    )
    (net (code "45") (name "Net-(D26-ANODE)") (class "Default")
      (node (ref "D26") (pin "1") (pinfunction "ANODE_1") (pintype "passive"))
      (node (ref "S26") (pin "1") (pinfunction "1_1") (pintype "passive"))
    )
    (net (code "46") (name "Net-(D27-ANODE)") (class "Default")
      (node (ref "D27") (pin "1") (pinfunction "ANODE_1") (pintype "passive"))
      (node (ref "S27") (pin "1") (pinfunction "1_1") (pintype "passive"))
    )
    (net (code "47") (name "Net-(D28-ANODE)") (class "Default")
      (node (ref "D28") (pin "1") (pinfunction "ANODE_1") (pintype "passive"))
      (node (ref "S28") (pin "1") (pinfunction "1_1") (pintype "passive"))
    )
    (net (code "48") (name "Net-(D29-ANODE)") (class "Default")
      (node (ref "D29") (pin "1") (pinfunction "ANODE_1") (pintype "passive"))
      (node (ref "S29") (pin "1") (pinfunction "1_1") (pintype "passive"))
    )
    (net (code "49") (name "Net-(D30-ANODE)") (class "Default")
      (node (ref "D30") (pin "1") (pinfunction "ANODE_1") (pintype "passive"))
      (node (ref "S30") (pin "1") (pinfunction "1_1") (pintype "passive"))
    )
    (net (code "50") (name "Net-(D31-ANODE)") (class "Default")
      (node (ref "D31") (pin "1") (pinfunction "ANODE_1") (pintype "passive"))
      (node (ref "S31") (pin "1") (pinfunction "1_1") (pintype "passive"))
    )
    (net (code "51") (name "Net-(D32-ANODE)") (class "Default")
      (node (ref "D32") (pin "1") (pinfunction "ANODE_1") (pintype "passive"))
      (node (ref "S32") (pin "1") (pinfunction "1_1") (pintype "passive"))
    )
    (net (code "52") (name "Net-(D33-ANODE)") (class "Default")
      (node (ref "D33") (pin "1") (pinfunction "ANODE_1") (pintype "passive"))
      (node (ref "S33") (pin "1") (pinfunction "1_1") (pintype "passive"))
    )
    (net (code "53") (name "Net-(D34-ANODE)") (class "Default")
      (node (ref "D34") (pin "1") (pinfunction "ANODE_1") (pintype "passive"))
      (node (ref "S34") (pin "1") (pinfunction "1_1") (pintype "passive"))
    )
    (net (code "54") (name "Net-(D35-ANODE)") (class "Default")
      (node (ref "D35") (pin "1") (pinfunction "ANODE_1") (pintype "passive"))
      (node (ref "S35") (pin "1") (pinfunction "1_1") (pintype "passive"))
    )
    (net (code "55") (name "Net-(D36-ANODE)") (class "Default")
      (node (ref "D36") (pin "1") (pinfunction "ANODE_1") (pintype "passive"))
      (node (ref "S36") (pin "1") (pinfunction "1_1") (pintype "passive"))
    )
    (net (code "56") (name "Net-(D37-ANODE)") (class "Default")
      (node (ref "D37") (pin "1") (pinfunction "ANODE_1") (pintype "passive"))
      (node (ref "S37") (pin "1") (pinfunction "1_1") (pintype "passive"))
    )
    (net (code "57") (name "Net-(D38-ANODE)") (class "Default")
      (node (ref "D38") (pin "1") (pinfunction "ANODE_1") (pintype "passive"))
      (node (ref "S38") (pin "1") (pinfunction "1_1") (pintype "passive"))
    )
    (net (code "58") (name "Net-(D39-ANODE)") (class "Default")
      (node (ref "D39") (pin "1") (pinfunction "ANODE_1") (pintype "passive"))
      (node (ref "S39") (pin "1") (pinfunction "1_1") (pintype "passive"))
    )
    (net (code "59") (name "Net-(D40-ANODE)") (class "Default")
      (node (ref "D40") (pin "1") (pinfunction "ANODE_1") (pintype "passive"))
      (node (ref "S40") (pin "1") (pinfunction "1_1") (pintype "passive"))
    )
    (net (code "60") (name "Net-(D41-ANODE)") (class "Default")
      (node (ref "D41") (pin "1") (pinfunction "ANODE_1") (pintype "passive"))
      (node (ref "S41") (pin "1") (pinfunction "1_1") (pintype "passive"))
    )
    (net (code "61") (name "Net-(D42-ANODE)") (class "Default")
      (node (ref "D42") (pin "1") (pinfunction "ANODE_1") (pintype "passive"))
      (node (ref "S42") (pin "1") (pinfunction "1_1") (pintype "passive"))
    )
    (net (code "62") (name "Net-(D43-ANODE)") (class "Default")
      (node (ref "D43") (pin "1") (pinfunction "ANODE_1") (pintype "passive"))
      (node (ref "S43") (pin "1") (pinfunction "1_1") (pintype "passive"))
    )
    (net (code "63") (name "Net-(D44-ANODE)") (class "Default")
      (node (ref "D44") (pin "1") (pinfunction "ANODE_1") (pintype "passive"))
      (node (ref "S44") (pin "1") (pinfunction "1_1") (pintype "passive"))
    )
    (net (code "64") (name "Net-(D45-ANODE)") (class "Default")
      (node (ref "D45") (pin "1") (pinfunction "ANODE_1") (pintype "passive"))
      (node (ref "S45") (pin "1") (pinfunction "1_1") (pintype "passive"))
    )
    (net (code "65") (name "Net-(D46-ANODE)") (class "Default")
      (node (ref "D46") (pin "1") (pinfunction "ANODE_1") (pintype "passive"))
      (node (ref "S46") (pin "1") (pinfunction "1_1") (pintype "passive"))
    )
    (net (code "66") (name "Net-(D47-ANODE)") (class "Default")
      (node (ref "D47") (pin "1") (pinfunction "ANODE_1") (pintype "passive"))
      (node (ref "S47") (pin "1") (pinfunction "1_1") (pintype "passive"))
    )
    (net (code "67") (name "Net-(D48-ANODE)") (class "Default")
      (node (ref "D48") (pin "1") (pinfunction "ANODE_1") (pintype "passive"))
      (node (ref "S48") (pin "1") (pinfunction "1_1") (pintype "passive"))
    )
    (net (code "68") (name "Net-(D49-ANODE)") (class "Default")
      (node (ref "D49") (pin "1") (pinfunction "ANODE_1") (pintype "passive"))
      (node (ref "S49") (pin "1") (pinfunction "1_1") (pintype "passive"))
    )
    (net (code "69") (name "Net-(D50-ANODE)") (class "Default")
      (node (ref "D50") (pin "1") (pinfunction "ANODE_1") (pintype "passive"))
      (node (ref "S50") (pin "1") (pinfunction "1_1") (pintype "passive"))
    )
    (net (code "70") (name "Net-(D51-ANODE)") (class "Default")
      (node (ref "D51") (pin "1") (pinfunction "ANODE_1") (pintype "passive"))
      (node (ref "S51") (pin "1") (pinfunction "1_1") (pintype "passive"))
    )
    (net (code "71") (name "Net-(D52-ANODE)") (class "Default")
      (node (ref "D52") (pin "1") (pinfunction "ANODE_1") (pintype "passive"))
      (node (ref "S52") (pin "1") (pinfunction "1_1") (pintype "passive"))
    )
    (net (code "72") (name "Net-(D53-ANODE)") (class "Default")
      (node (ref "D53") (pin "1") (pinfunction "ANODE_1") (pintype "passive"))
      (node (ref "S53") (pin "1") (pinfunction "1_1") (pintype "passive"))
    )
    (net (code "73") (name "Net-(D54-ANODE)") (class "Default")
      (node (ref "D54") (pin "1") (pinfunction "ANODE_1") (pintype "passive"))
      (node (ref "S54") (pin "1") (pinfunction "1_1") (pintype "passive"))
    )
    (net (code "74") (name "Net-(D55-ANODE)") (class "Default")
      (node (ref "D55") (pin "1") (pinfunction "ANODE_1") (pintype "passive"))
      (node (ref "S55") (pin "1") (pinfunction "1_1") (pintype "passive"))
    )
    (net (code "75") (name "Net-(D56-ANODE)") (class "Default")
      (node (ref "D56") (pin "1") (pinfunction "ANODE_1") (pintype "passive"))
      (node (ref "S56") (pin "1") (pinfunction "1_1") (pintype "passive"))
    )
    (net (code "76") (name "Net-(D57-ANODE)") (class "Default")
      (node (ref "D57") (pin "1") (pinfunction "ANODE_1") (pintype "passive"))
      (node (ref "S57") (pin "1") (pinfunction "1_1") (pintype "passive"))
    )
    (net (code "77") (name "Net-(D58-ANODE)") (class "Default")
      (node (ref "D58") (pin "1") (pinfunction "ANODE_1") (pintype "passive"))
      (node (ref "S58") (pin "1") (pinfunction "1_1") (pintype "passive"))
    )
    (net (code "78") (name "Net-(D59-ANODE)") (class "Default")
      (node (ref "D59") (pin "1") (pinfunction "ANODE_1") (pintype "passive"))
      (node (ref "S59") (pin "1") (pinfunction "1_1") (pintype "passive"))
    )
    (net (code "79") (name "Net-(D60-ANODE)") (class "Default")
      (node (ref "D60") (pin "1") (pinfunction "ANODE_1") (pintype "passive"))
      (node (ref "S60") (pin "1") (pinfunction "1_1") (pintype "passive"))
    )
    (net (code "80") (name "Net-(D61-ANODE)") (class "Default")
      (node (ref "D61") (pin "1") (pinfunction "ANODE_1") (pintype "passive"))
      (node (ref "S61") (pin "1") (pinfunction "1_1") (pintype "passive"))
    )
    (net (code "81") (name "Net-(D62-ANODE)") (class "Default")
      (node (ref "D62") (pin "1") (pinfunction "ANODE_1") (pintype "passive"))
      (node (ref "S62") (pin "1") (pinfunction "1_1") (pintype "passive"))
    )
    (net (code "82") (name "Net-(D63-ANODE)") (class "Default")
      (node (ref "D63") (pin "1") (pinfunction "ANODE_1") (pintype "passive"))
      (node (ref "S63") (pin "1") (pinfunction "1_1") (pintype "passive"))
    )
    (net (code "83") (name "Net-(D64-ANODE)") (class "Default")
      (node (ref "D64") (pin "1") (pinfunction "ANODE_1") (pintype "passive"))
      (node (ref "S64") (pin "1") (pinfunction "1_1") (pintype "passive"))
    )
  )
)
